# Industrial-Controller_Input.net
KiCad netlist of a schematic drawn in Altium Designer
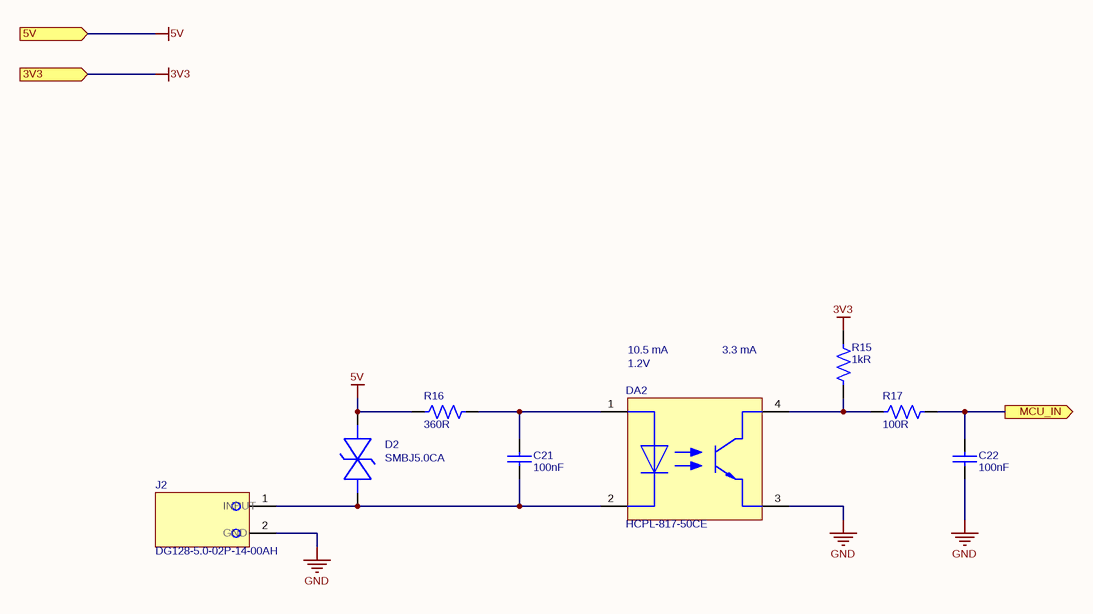
[diagram p0: Industrial-Controller_Input.SchDoc]

(export (version "E")
  (design (tool "Eeschema 10.0.6"))
  (components
    (comp (ref "C21")
      (value "100nF")
      (footprint "CAP_0603")
      (description "CAP CER 0.1UF 50V X7R 0603")
      (fields (field (name "TOLERANCE") "10%"))
      (libsource (lib "Industrial-Controller") (part "CL10B104KB8NNNL"))
    )
    (comp (ref "C22")
      (value "100nF")
      (footprint "CAP_0603")
      (description "CAP CER 0.1UF 50V X7R 0603")
      (fields (field (name "TOLERANCE") "10%"))
      (libsource (lib "Industrial-Controller") (part "CL10B104KB8NNNL"))
    )
    (comp (ref "D2")
      (value "SMBJ5.0CA")
      (footprint "SMB-BIDIR")
      (description "TVS DIODE 5VWM 9.2VC SMB")
      (libsource (lib "Industrial-Controller") (part "SMBJ5.0CA"))
    )
    (comp (ref "DA2")
      (value "HCPL-817-50CE")
      (footprint "HCPL-817-50CE")
      (description "OPTOISOLATOR 5KV TRANSISTOR 4SMD")
      (libsource (lib "Industrial-Controller") (part "HCPL-817-50CE"))
    )
    (comp (ref "J2")
      (value "DG128-5.0-02P-14-00AH")
      (footprint "DG128-5.0-02P-14")
      (description "TERM BLK 2P TOP ENTRY 5MM SMD")
      (libsource (lib "Industrial-Controller") (part "DG128-5.0-02P-14"))
    )
    (comp (ref "R15")
      (value "1kR")
      (footprint "RES_0603")
      (description "RES 1K OHM 1% 1/10W 0603")
      (fields (field (name "TOLERANCE") "1%"))
      (libsource (lib "Industrial-Controller") (part "RC0603FR-071KL"))
    )
    (comp (ref "R16")
      (value "360R")
      (footprint "RES_0603")
      (description "RES 360 OHM 1% 1/10W 0603")
      (fields (field (name "TOLERANCE") "1%"))
      (libsource (lib "Industrial-Controller") (part "RC0603FR-07360RL"))
    )
    (comp (ref "R17")
      (value "100R")
      (footprint "RES_0603")
      (description "RES 100 OHM 1% 1/10W 0603")
      (fields (field (name "TOLERANCE") "1%"))
      (libsource (lib "Industrial-Controller") (part "RC0603FR-07100RL"))
    )
  )
  (nets
    (net (code "1") (name "/MCU_IN") (class "Default")
      (node (ref "C22") (pin "1") (pinfunction "1_1") (pintype "passive"))
      (node (ref "R17") (pin "1") (pinfunction "1_1") (pintype "passive"))
    )
    (net (code "2") (name "3V3") (class "Default")
      (node (ref "R15") (pin "1") (pinfunction "1_1") (pintype "passive"))
    )
    (net (code "3") (name "5V") (class "Default")
      (node (ref "D2") (pin "1") (pinfunction "1_1") (pintype "passive"))
      (node (ref "R16") (pin "1") (pinfunction "1_1") (pintype "passive"))
    )
    (net (code "4") (name "GND") (class "Default")
      (node (ref "C22") (pin "2") (pinfunction "2_2") (pintype "passive"))
      (node (ref "DA2") (pin "3") (pinfunction "EMITTER_3") (pintype "passive"))
      (node (ref "J2") (pin "2") (pinfunction "2_2") (pintype "passive"))
    )
    (net (code "5") (name "Net-(DA2-ANODE)") (class "Default")
      (node (ref "C21") (pin "1") (pinfunction "1_1") (pintype "passive"))
      (node (ref "DA2") (pin "1") (pinfunction "ANODE_1") (pintype "passive"))
      (node (ref "R16") (pin "2") (pinfunction "2_2") (pintype "passive"))
    )
    (net (code "6") (name "Net-(DA2-CATHODE)") (class "Default")
      (node (ref "C21") (pin "2") (pinfunction "2_2") (pintype "passive"))
      (node (ref "D2") (pin "2") (pinfunction "2_2") (pintype "passive"))
      (node (ref "DA2") (pin "2") (pinfunction "CATHODE_2") (pintype "passive"))
      (node (ref "J2") (pin "1") (pinfunction "1_1") (pintype "passive"))
    )
    (net (code "7") (name "Net-(DA2-COLLECTOR)") (class "Default")
      (node (ref "DA2") (pin "4") (pinfunction "COLLECTOR_4") (pintype "passive"))
      (node (ref "R15") (pin "2") (pinfunction "2_2") (pintype "passive"))
      (node (ref "R17") (pin "2") (pinfunction "2_2") (pintype "passive"))
    )
  )
)
